# SmartMirror.net
KiCad netlist of a schematic drawn in EAGLE
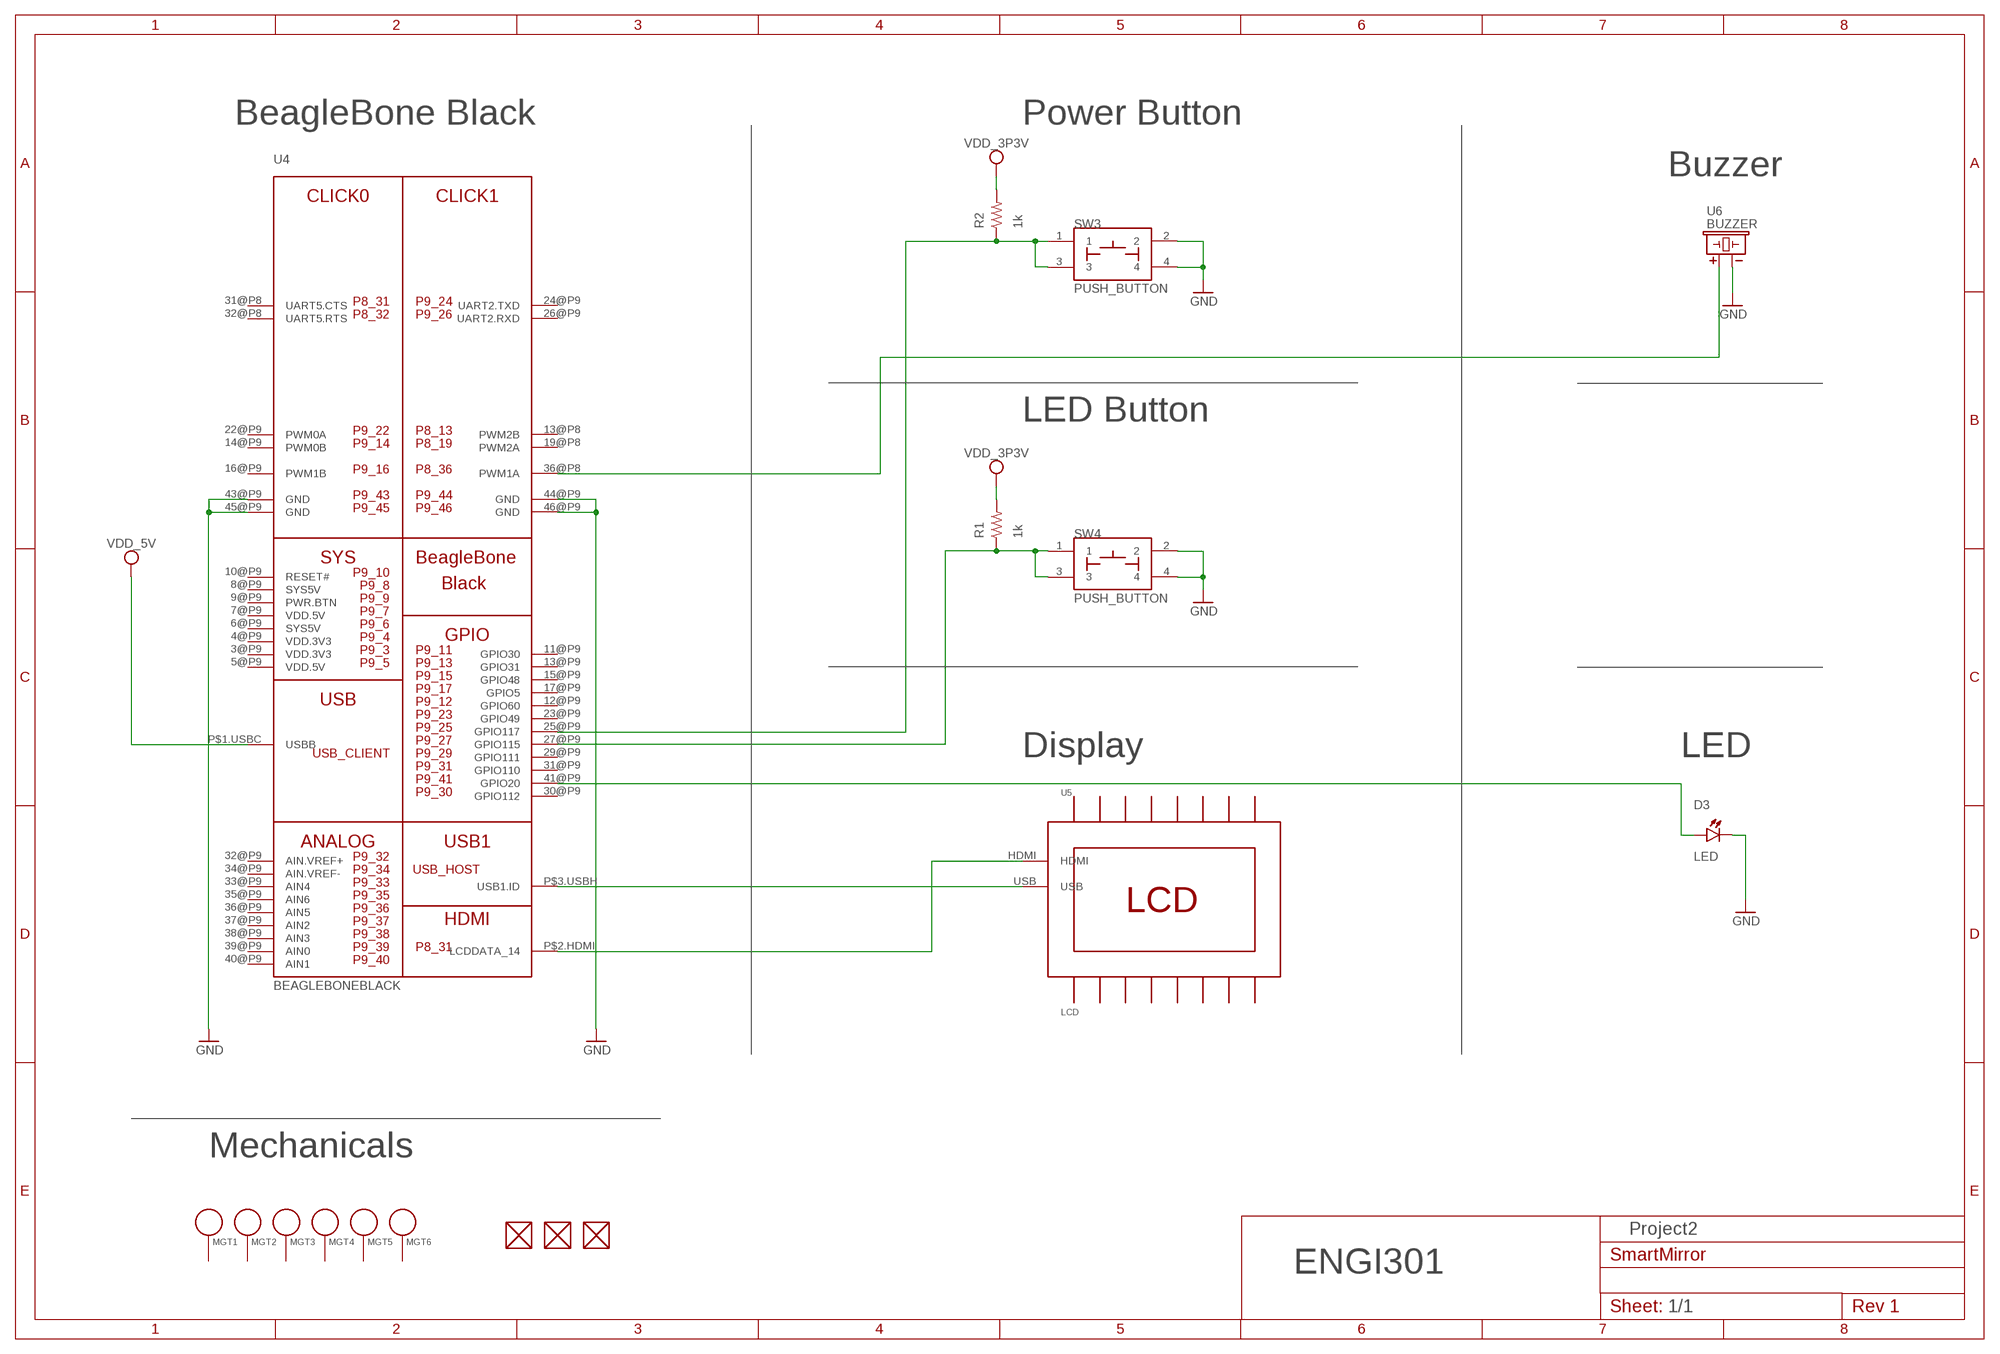
[diagram p0: schematic, sheet 1]

(export (version "E")
  (design (tool "Eeschema 10.0.6"))
  (components
    (comp (ref "D3")
      (value "LED")
      (footprint "eagle-import:EIA-STD")
      (libsource (lib "eagle-import") (part "LED"))
    )
    (comp (ref "FUD1")
      (value "FIDUCIAL")
      (footprint "eagle-import:FIDUCIAL_40MIL")
      (libsource (lib "eagle-import") (part "FIDUCIAL"))
    )
    (comp (ref "FUD2")
      (value "FIDUCIAL")
      (footprint "eagle-import:FIDUCIAL_40MIL")
      (libsource (lib "eagle-import") (part "FIDUCIAL"))
    )
    (comp (ref "FUD3")
      (value "FIDUCIAL")
      (footprint "eagle-import:FIDUCIAL_40MIL")
      (libsource (lib "eagle-import") (part "FIDUCIAL"))
    )
    (comp (ref "MGT1")
      (value "MOUNTING_HOLE")
      (footprint "eagle-import:MOUNTING_HOLE")
      (libsource (lib "eagle-import") (part "MOUNTING_HOLE"))
    )
    (comp (ref "MGT2")
      (value "MOUNTING_HOLE")
      (footprint "eagle-import:MOUNTING_HOLE")
      (libsource (lib "eagle-import") (part "MOUNTING_HOLE"))
    )
    (comp (ref "MGT3")
      (value "MOUNTING_HOLE")
      (footprint "eagle-import:MOUNTING_HOLE")
      (libsource (lib "eagle-import") (part "MOUNTING_HOLE"))
    )
    (comp (ref "MGT4")
      (value "MOUNTING_HOLE")
      (footprint "eagle-import:MOUNTING_HOLE")
      (libsource (lib "eagle-import") (part "MOUNTING_HOLE"))
    )
    (comp (ref "MGT5")
      (value "MOUNTING_HOLE")
      (footprint "eagle-import:MOUNTING_HOLE")
      (libsource (lib "eagle-import") (part "MOUNTING_HOLE"))
    )
    (comp (ref "MGT6")
      (value "MOUNTING_HOLE")
      (footprint "eagle-import:MOUNTING_HOLE")
      (libsource (lib "eagle-import") (part "MOUNTING_HOLE"))
    )
    (comp (ref "R1")
      (value "1k")
      (footprint "eagle-import:R0402")
      (libsource (lib "eagle-import") (part "R_R0402"))
    )
    (comp (ref "R2")
      (value "1k")
      (footprint "eagle-import:R0402")
      (libsource (lib "eagle-import") (part "R_R0402"))
    )
    (comp (ref "SW3")
      (value "PUSH_BUTTON")
      (footprint "eagle-import:BUTTON_12.5MM")
      (libsource (lib "eagle-import") (part "PUSH_BUTTON"))
    )
    (comp (ref "SW4")
      (value "PUSH_BUTTON")
      (footprint "eagle-import:BUTTON_12.5MM")
      (libsource (lib "eagle-import") (part "PUSH_BUTTON"))
    )
    (comp (ref "U4")
      (value "BEAGLEBONEBLACK")
      (footprint "eagle-import:BEAGLEBONEBLACK")
      (libsource (lib "eagle-import") (part "BEAGLEBONEBLACK"))
    )
    (comp (ref "U5")
      (value "LCD")
      (footprint "eagle-import:LCD")
      (libsource (lib "eagle-import") (part "LCD"))
    )
    (comp (ref "U6")
      (value "BUZZER")
      (footprint "eagle-import:BUZZER_6.5MM")
      (libsource (lib "eagle-import") (part "BUZZER"))
    )
  )
  (nets
    (net (code "1") (name "/SYS5V") (class "Default")
      (node (ref "U4") (pin "6@P9") (pinfunction "SYS5V_6@P9") (pintype "power_in"))
    )
    (net (code "2") (name "/VDD.3V3") (class "Default")
      (node (ref "U4") (pin "3@P9") (pinfunction "VDD.3V3_3@P9") (pintype "power_in"))
    )
    (net (code "3") (name "GND") (class "Default")
      (node (ref "D3") (pin "CATHODE") (pinfunction "CATHODE_CATHODE") (pintype "bidirectional"))
      (node (ref "SW3") (pin "2") (pinfunction "2_2") (pintype "bidirectional"))
      (node (ref "SW3") (pin "4") (pinfunction "4_4") (pintype "bidirectional"))
      (node (ref "SW4") (pin "2") (pinfunction "2_2") (pintype "bidirectional"))
      (node (ref "SW4") (pin "4") (pinfunction "4_4") (pintype "bidirectional"))
      (node (ref "U4") (pin "43@P9") (pinfunction "GND_43@P9") (pintype "power_in"))
      (node (ref "U4") (pin "44@P9") (pinfunction "GND_44@P9") (pintype "power_in"))
      (node (ref "U4") (pin "45@P9") (pinfunction "GND_45@P9") (pintype "power_in"))
      (node (ref "U4") (pin "46@P9") (pinfunction "GND_46@P9") (pintype "power_in"))
      (node (ref "U6") (pin "-") (pinfunction "-_-") (pintype "passive"))
    )
    (net (code "4") (name "Net-(U4-GPIO20)") (class "Default")
      (node (ref "D3") (pin "ANODE") (pinfunction "ANODE_ANODE") (pintype "bidirectional"))
      (node (ref "U4") (pin "41@P9") (pinfunction "GPIO20_41@P9") (pintype "bidirectional"))
    )
    (net (code "5") (name "Net-(U4-GPIO115)") (class "Default")
      (node (ref "R1") (pin "1") (pinfunction "1_1") (pintype "passive"))
      (node (ref "SW4") (pin "1") (pinfunction "1_1") (pintype "bidirectional"))
      (node (ref "SW4") (pin "3") (pinfunction "3_3") (pintype "bidirectional"))
      (node (ref "U4") (pin "27@P9") (pinfunction "GPIO115_27@P9") (pintype "bidirectional"))
    )
    (net (code "6") (name "Net-(U4-GPIO117)") (class "Default")
      (node (ref "R2") (pin "1") (pinfunction "1_1") (pintype "passive"))
      (node (ref "SW3") (pin "1") (pinfunction "1_1") (pintype "bidirectional"))
      (node (ref "SW3") (pin "3") (pinfunction "3_3") (pintype "bidirectional"))
      (node (ref "U4") (pin "25@P9") (pinfunction "GPIO117_25@P9") (pintype "bidirectional"))
    )
    (net (code "7") (name "Net-(U4-LCDDATA_14)") (class "Default")
      (node (ref "U4") (pin "P$2.HDMI") (pinfunction "LCDDATA_14_P$2.HDMI") (pintype "bidirectional"))
      (node (ref "U5") (pin "HDMI") (pinfunction "HDMI_HDMI") (pintype "bidirectional"))
    )
    (net (code "8") (name "Net-(U4-PWM1A)") (class "Default")
      (node (ref "U4") (pin "36@P8") (pinfunction "PWM1A_36@P8") (pintype "bidirectional"))
      (node (ref "U6") (pin "+") (pinfunction "+_+") (pintype "passive"))
    )
    (net (code "9") (name "Net-(U4-USB1.ID)") (class "Default")
      (node (ref "U4") (pin "P$3.USBH") (pinfunction "USB1.ID_P$3.USBH") (pintype "bidirectional"))
      (node (ref "U5") (pin "USB") (pinfunction "USB_USB") (pintype "bidirectional"))
    )
    (net (code "10") (name "VDD_3P3V") (class "Default")
      (node (ref "R1") (pin "2") (pinfunction "2_2") (pintype "passive"))
      (node (ref "R2") (pin "2") (pinfunction "2_2") (pintype "passive"))
    )
    (net (code "11") (name "VDD_5V") (class "Default")
      (node (ref "U4") (pin "P$1.USBC") (pinfunction "USBB_P$1.USBC") (pintype "bidirectional"))
    )
    (net (code "12") (name "unconnected-(FUD1-PadP$1)") (class "Default")
      (node (ref "FUD1") (pin "P$1") (pinfunction "P$1_P$1") (pintype "no_connect"))
    )
    (net (code "13") (name "unconnected-(FUD2-PadP$1)") (class "Default")
      (node (ref "FUD2") (pin "P$1") (pinfunction "P$1_P$1") (pintype "no_connect"))
    )
    (net (code "14") (name "unconnected-(FUD3-PadP$1)") (class "Default")
      (node (ref "FUD3") (pin "P$1") (pinfunction "P$1_P$1") (pintype "no_connect"))
    )
    (net (code "15") (name "unconnected-(MGT1-PadP$1)") (class "Default")
      (node (ref "MGT1") (pin "P$1") (pinfunction "P$1_P$1") (pintype "bidirectional"))
    )
    (net (code "16") (name "unconnected-(MGT2-PadP$1)") (class "Default")
      (node (ref "MGT2") (pin "P$1") (pinfunction "P$1_P$1") (pintype "bidirectional"))
    )
    (net (code "17") (name "unconnected-(MGT3-PadP$1)") (class "Default")
      (node (ref "MGT3") (pin "P$1") (pinfunction "P$1_P$1") (pintype "bidirectional"))
    )
    (net (code "18") (name "unconnected-(MGT4-PadP$1)") (class "Default")
      (node (ref "MGT4") (pin "P$1") (pinfunction "P$1_P$1") (pintype "bidirectional"))
    )
    (net (code "19") (name "unconnected-(MGT5-PadP$1)") (class "Default")
      (node (ref "MGT5") (pin "P$1") (pinfunction "P$1_P$1") (pintype "bidirectional"))
    )
    (net (code "20") (name "unconnected-(MGT6-PadP$1)") (class "Default")
      (node (ref "MGT6") (pin "P$1") (pinfunction "P$1_P$1") (pintype "bidirectional"))
    )
    (net (code "21") (name "unconnected-(U4-AIN.VREF+-Pad32@P9)") (class "Default")
      (node (ref "U4") (pin "32@P9") (pinfunction "AIN.VREF+_32@P9") (pintype "input"))
    )
    (net (code "22") (name "unconnected-(U4-AIN.VREF--Pad34@P9)") (class "Default")
      (node (ref "U4") (pin "34@P9") (pinfunction "AIN.VREF-_34@P9") (pintype "input"))
    )
    (net (code "23") (name "unconnected-(U4-AIN0-Pad39@P9)") (class "Default")
      (node (ref "U4") (pin "39@P9") (pinfunction "AIN0_39@P9") (pintype "input"))
    )
    (net (code "24") (name "unconnected-(U4-AIN1-Pad40@P9)") (class "Default")
      (node (ref "U4") (pin "40@P9") (pinfunction "AIN1_40@P9") (pintype "bidirectional"))
    )
    (net (code "25") (name "unconnected-(U4-AIN2-Pad37@P9)") (class "Default")
      (node (ref "U4") (pin "37@P9") (pinfunction "AIN2_37@P9") (pintype "input"))
    )
    (net (code "26") (name "unconnected-(U4-AIN3-Pad38@P9)") (class "Default")
      (node (ref "U4") (pin "38@P9") (pinfunction "AIN3_38@P9") (pintype "input"))
    )
    (net (code "27") (name "unconnected-(U4-AIN4-Pad33@P9)") (class "Default")
      (node (ref "U4") (pin "33@P9") (pinfunction "AIN4_33@P9") (pintype "input"))
    )
    (net (code "28") (name "unconnected-(U4-AIN5-Pad36@P9)") (class "Default")
      (node (ref "U4") (pin "36@P9") (pinfunction "AIN5_36@P9") (pintype "input"))
    )
    (net (code "29") (name "unconnected-(U4-AIN6-Pad35@P9)") (class "Default")
      (node (ref "U4") (pin "35@P9") (pinfunction "AIN6_35@P9") (pintype "input"))
    )
    (net (code "30") (name "unconnected-(U4-GPIO5-Pad17@P9)") (class "Default")
      (node (ref "U4") (pin "17@P9") (pinfunction "GPIO5_17@P9") (pintype "bidirectional"))
    )
    (net (code "31") (name "unconnected-(U4-GPIO30-Pad11@P9)") (class "Default")
      (node (ref "U4") (pin "11@P9") (pinfunction "GPIO30_11@P9") (pintype "bidirectional"))
    )
    (net (code "32") (name "unconnected-(U4-GPIO31-Pad13@P9)") (class "Default")
      (node (ref "U4") (pin "13@P9") (pinfunction "GPIO31_13@P9") (pintype "bidirectional"))
    )
    (net (code "33") (name "unconnected-(U4-GPIO48-Pad15@P9)") (class "Default")
      (node (ref "U4") (pin "15@P9") (pinfunction "GPIO48_15@P9") (pintype "bidirectional"))
    )
    (net (code "34") (name "unconnected-(U4-GPIO49-Pad23@P9)") (class "Default")
      (node (ref "U4") (pin "23@P9") (pinfunction "GPIO49_23@P9") (pintype "bidirectional"))
    )
    (net (code "35") (name "unconnected-(U4-GPIO60-Pad12@P9)") (class "Default")
      (node (ref "U4") (pin "12@P9") (pinfunction "GPIO60_12@P9") (pintype "bidirectional"))
    )
    (net (code "36") (name "unconnected-(U4-GPIO110-Pad31@P9)") (class "Default")
      (node (ref "U4") (pin "31@P9") (pinfunction "GPIO110_31@P9") (pintype "bidirectional"))
    )
    (net (code "37") (name "unconnected-(U4-GPIO111-Pad29@P9)") (class "Default")
      (node (ref "U4") (pin "29@P9") (pinfunction "GPIO111_29@P9") (pintype "bidirectional"))
    )
    (net (code "38") (name "unconnected-(U4-GPIO112-Pad30@P9)") (class "Default")
      (node (ref "U4") (pin "30@P9") (pinfunction "GPIO112_30@P9") (pintype "bidirectional"))
    )
    (net (code "39") (name "unconnected-(U4-PWM0A-Pad22@P9)") (class "Default")
      (node (ref "U4") (pin "22@P9") (pinfunction "PWM0A_22@P9") (pintype "bidirectional"))
    )
    (net (code "40") (name "unconnected-(U4-PWM0B-Pad14@P9)") (class "Default")
      (node (ref "U4") (pin "14@P9") (pinfunction "PWM0B_14@P9") (pintype "bidirectional"))
    )
    (net (code "41") (name "unconnected-(U4-PWM1B-Pad16@P9)") (class "Default")
      (node (ref "U4") (pin "16@P9") (pinfunction "PWM1B_16@P9") (pintype "bidirectional"))
    )
    (net (code "42") (name "unconnected-(U4-PWM2A-Pad19@P8)") (class "Default")
      (node (ref "U4") (pin "19@P8") (pinfunction "PWM2A_19@P8") (pintype "bidirectional"))
    )
    (net (code "43") (name "unconnected-(U4-PWM2B-Pad13@P8)") (class "Default")
      (node (ref "U4") (pin "13@P8") (pinfunction "PWM2B_13@P8") (pintype "bidirectional"))
    )
    (net (code "44") (name "unconnected-(U4-PWR.BTN-Pad9@P9)") (class "Default")
      (node (ref "U4") (pin "9@P9") (pinfunction "PWR.BTN_9@P9") (pintype "input"))
    )
    (net (code "45") (name "unconnected-(U4-RESET#-Pad10@P9)") (class "Default")
      (node (ref "U4") (pin "10@P9") (pinfunction "RESET#_10@P9") (pintype "input"))
    )
    (net (code "46") (name "unconnected-(U4-SYS5V-Pad8@P9)") (class "Default")
      (node (ref "U4") (pin "8@P9") (pinfunction "SYS5V_8@P9") (pintype "bidirectional"))
    )
    (net (code "47") (name "unconnected-(U4-UART2.RXD-Pad26@P9)") (class "Default")
      (node (ref "U4") (pin "26@P9") (pinfunction "UART2.RXD_26@P9") (pintype "bidirectional"))
    )
    (net (code "48") (name "unconnected-(U4-UART2.TXD-Pad24@P9)") (class "Default")
      (node (ref "U4") (pin "24@P9") (pinfunction "UART2.TXD_24@P9") (pintype "bidirectional"))
    )
    (net (code "49") (name "unconnected-(U4-UART5.CTS-Pad31@P8)") (class "Default")
      (node (ref "U4") (pin "31@P8") (pinfunction "UART5.CTS_31@P8") (pintype "bidirectional"))
    )
    (net (code "50") (name "unconnected-(U4-UART5.RTS-Pad32@P8)") (class "Default")
      (node (ref "U4") (pin "32@P8") (pinfunction "UART5.RTS_32@P8") (pintype "bidirectional"))
    )
    (net (code "51") (name "unconnected-(U4-VDD.3V3-Pad4@P9)") (class "Default")
      (node (ref "U4") (pin "4@P9") (pinfunction "VDD.3V3_4@P9") (pintype "bidirectional"))
    )
    (net (code "52") (name "unconnected-(U4-VDD.5V-Pad5@P9)") (class "Default")
      (node (ref "U4") (pin "5@P9") (pinfunction "VDD.5V_5@P9") (pintype "input"))
    )
    (net (code "53") (name "unconnected-(U4-VDD.5V-Pad7@P9)") (class "Default")
      (node (ref "U4") (pin "7@P9") (pinfunction "VDD.5V_7@P9") (pintype "bidirectional"))
    )
  )
)
